# FPGA.net
KiCad netlist of a schematic drawn in Altium Designer
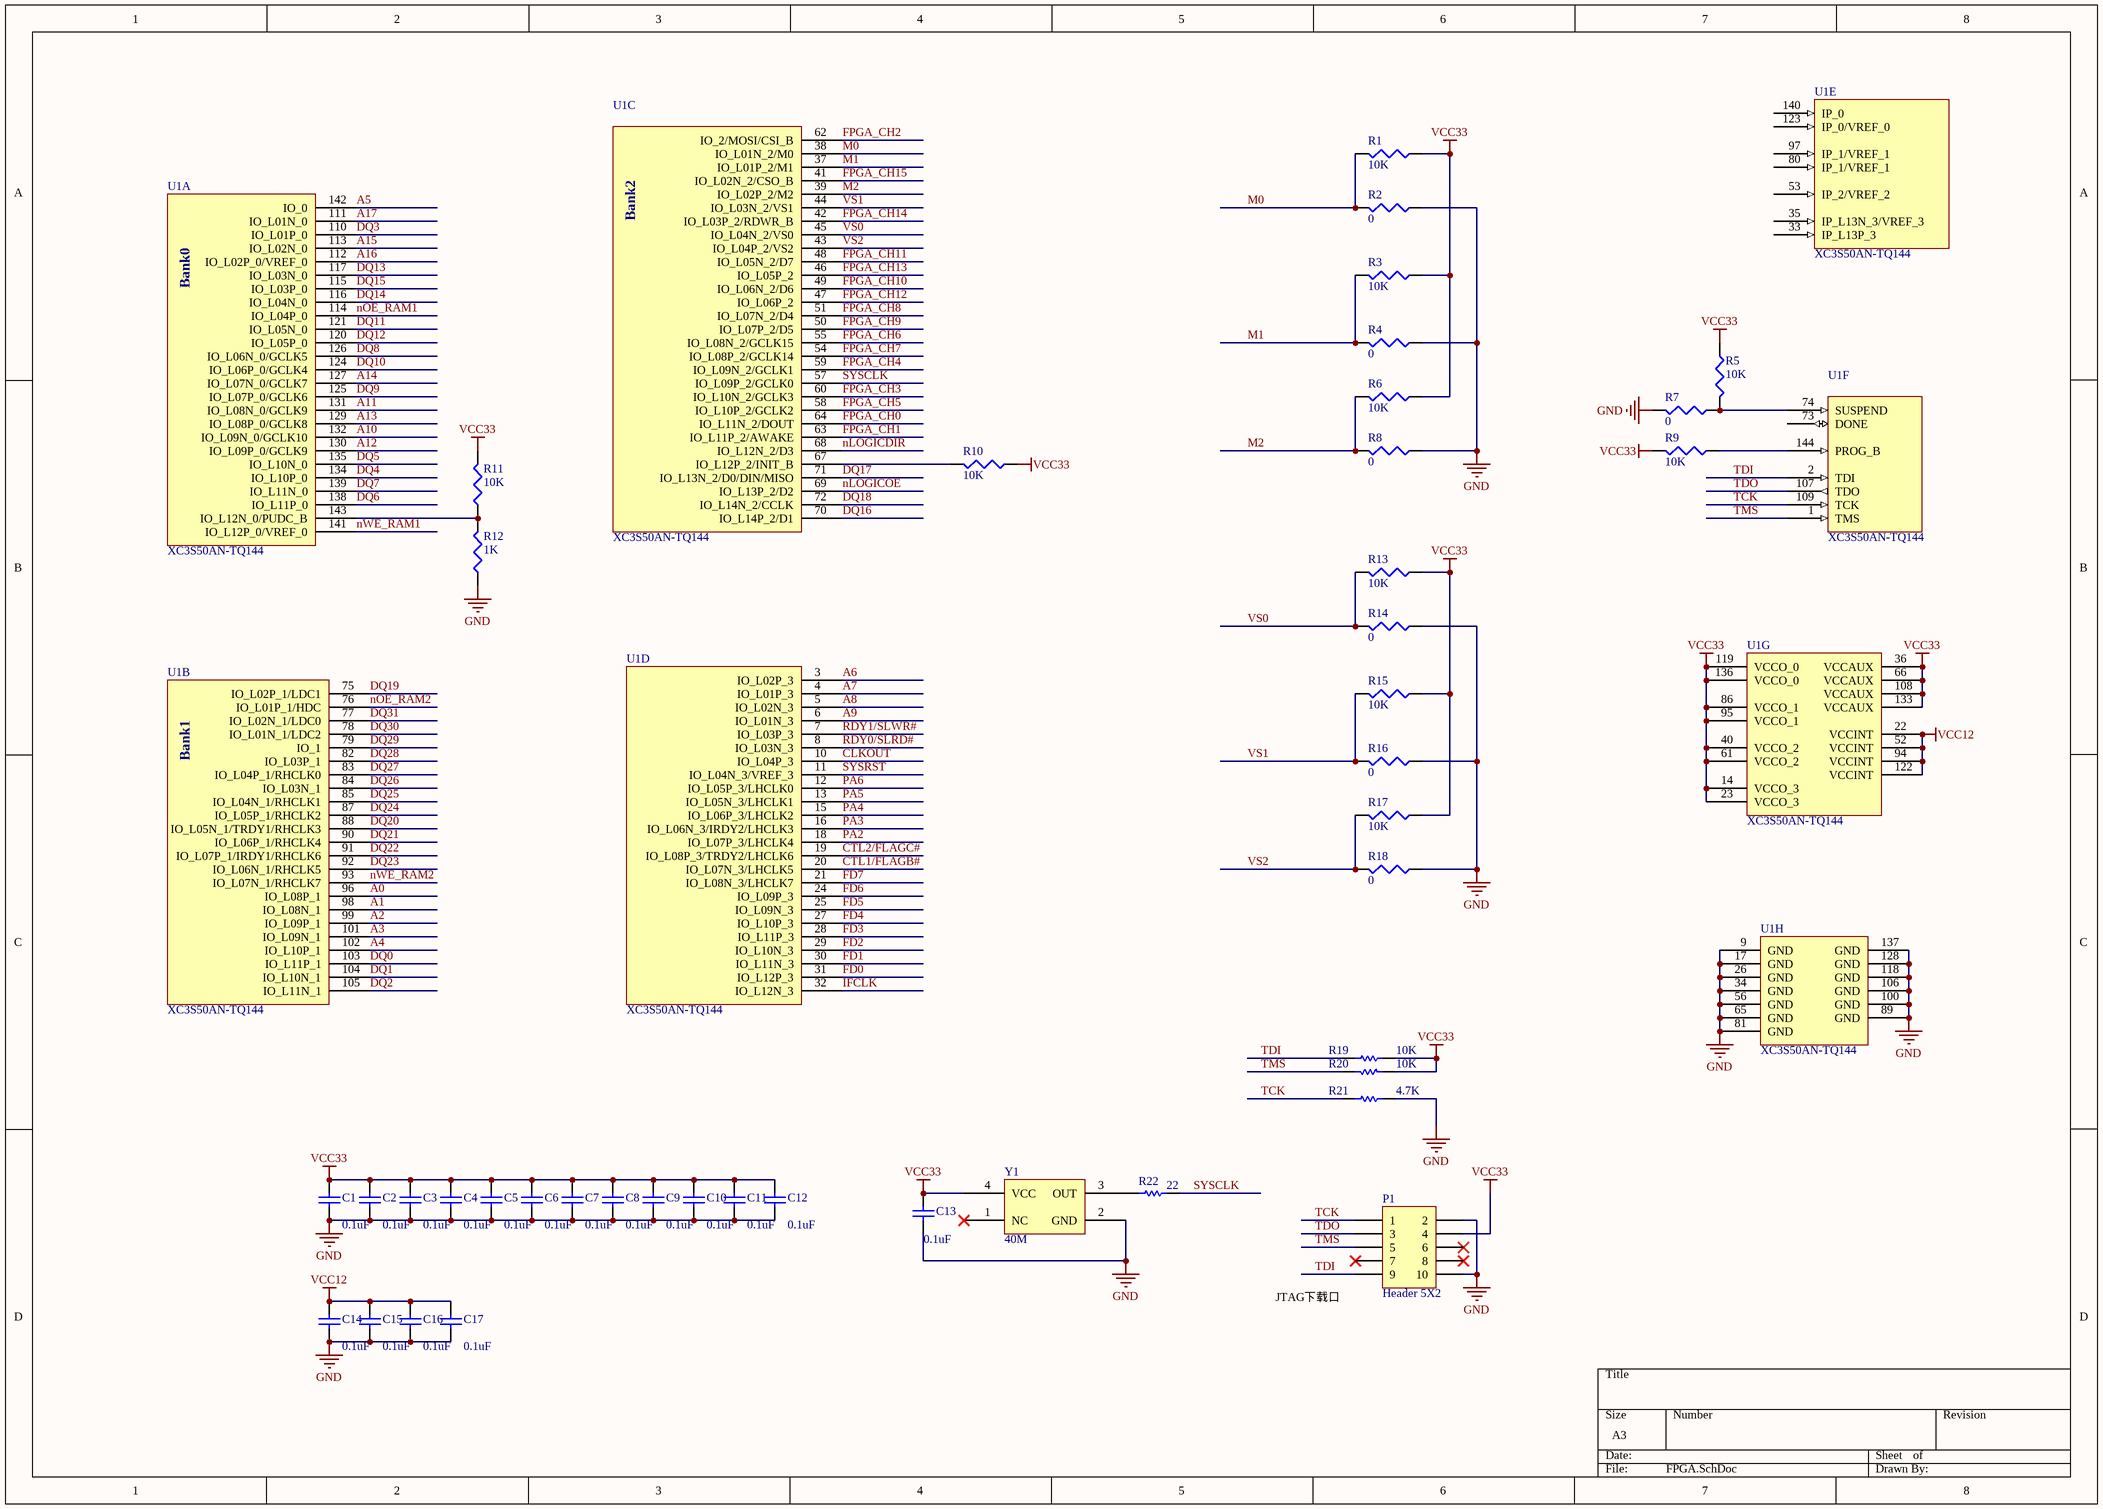
[diagram p0: FPGA.SchDoc]

(export (version "E")
  (design (tool "Eeschema 10.0.6"))
  (components
    (comp (ref "C1")
      (value "0.1uF")
      (footprint "cc0603")
      (description "Capacitor")
      (fields (field (name "PUBLISHER") "Altium Limited"))
      (libsource (lib "Miscellaneous Devices") (part "Cap"))
    )
    (comp (ref "C2")
      (value "0.1uF")
      (footprint "cc0603")
      (description "Capacitor")
      (fields (field (name "PUBLISHER") "Altium Limited"))
      (libsource (lib "Miscellaneous Devices") (part "Cap"))
    )
    (comp (ref "C3")
      (value "0.1uF")
      (footprint "cc0603")
      (description "Capacitor")
      (fields (field (name "PUBLISHER") "Altium Limited"))
      (libsource (lib "Miscellaneous Devices") (part "Cap"))
    )
    (comp (ref "C4")
      (value "0.1uF")
      (footprint "cc0603")
      (description "Capacitor")
      (fields (field (name "PUBLISHER") "Altium Limited"))
      (libsource (lib "Miscellaneous Devices") (part "Cap"))
    )
    (comp (ref "C5")
      (value "0.1uF")
      (footprint "cc0603")
      (description "Capacitor")
      (fields (field (name "PUBLISHER") "Altium Limited"))
      (libsource (lib "Miscellaneous Devices") (part "Cap"))
    )
    (comp (ref "C6")
      (value "0.1uF")
      (footprint "cc0603")
      (description "Capacitor")
      (fields (field (name "PUBLISHER") "Altium Limited"))
      (libsource (lib "Miscellaneous Devices") (part "Cap"))
    )
    (comp (ref "C7")
      (value "0.1uF")
      (footprint "cc0603")
      (description "Capacitor")
      (fields (field (name "PUBLISHER") "Altium Limited"))
      (libsource (lib "Miscellaneous Devices") (part "Cap"))
    )
    (comp (ref "C8")
      (value "0.1uF")
      (footprint "cc0603")
      (description "Capacitor")
      (fields (field (name "PUBLISHER") "Altium Limited"))
      (libsource (lib "Miscellaneous Devices") (part "Cap"))
    )
    (comp (ref "C9")
      (value "0.1uF")
      (footprint "cc0603")
      (description "Capacitor")
      (fields (field (name "PUBLISHER") "Altium Limited"))
      (libsource (lib "Miscellaneous Devices") (part "Cap"))
    )
    (comp (ref "C10")
      (value "0.1uF")
      (footprint "cc0603")
      (description "Capacitor")
      (fields (field (name "PUBLISHER") "Altium Limited"))
      (libsource (lib "Miscellaneous Devices") (part "Cap"))
    )
    (comp (ref "C11")
      (value "0.1uF")
      (footprint "cc0603")
      (description "Capacitor")
      (fields (field (name "PUBLISHER") "Altium Limited"))
      (libsource (lib "Miscellaneous Devices") (part "Cap"))
    )
    (comp (ref "C12")
      (value "0.1uF")
      (footprint "cc0603")
      (description "Capacitor")
      (fields (field (name "PUBLISHER") "Altium Limited"))
      (libsource (lib "Miscellaneous Devices") (part "Cap"))
    )
    (comp (ref "C13")
      (value "0.1uF")
      (footprint "cc0603")
      (description "Capacitor")
      (fields (field (name "PUBLISHER") "Altium Limited"))
      (libsource (lib "Miscellaneous Devices") (part "Cap"))
    )
    (comp (ref "C14")
      (value "0.1uF")
      (footprint "cc0603")
      (description "Capacitor")
      (fields (field (name "PUBLISHER") "Altium Limited"))
      (libsource (lib "Miscellaneous Devices") (part "Cap"))
    )
    (comp (ref "C15")
      (value "0.1uF")
      (footprint "cc0603")
      (description "Capacitor")
      (fields (field (name "PUBLISHER") "Altium Limited"))
      (libsource (lib "Miscellaneous Devices") (part "Cap"))
    )
    (comp (ref "C16")
      (value "0.1uF")
      (footprint "cc0603")
      (description "Capacitor")
      (fields (field (name "PUBLISHER") "Altium Limited"))
      (libsource (lib "Miscellaneous Devices") (part "Cap"))
    )
    (comp (ref "C17")
      (value "0.1uF")
      (footprint "cc0603")
      (description "Capacitor")
      (fields (field (name "PUBLISHER") "Altium Limited"))
      (libsource (lib "Miscellaneous Devices") (part "Cap"))
    )
    (comp (ref "P1")
      (value "Header 5X2")
      (footprint "HDR2X5")
      (description "Header, 5-Pin, Dual row")
      (fields (field (name "PUBLISHER") "Altium Limited"))
      (libsource (lib "Miscellaneous Connectors") (part "Header 5X2"))
    )
    (comp (ref "R1")
      (value "10K")
      (footprint "CR0603")
      (description "Resistor")
      (fields (field (name "PUBLISHER") "Altium Limited"))
      (libsource (lib "Miscellaneous Devices") (part "Res3"))
    )
    (comp (ref "R2")
      (value "0")
      (footprint "CR0603")
      (description "Resistor")
      (fields (field (name "PUBLISHER") "Altium Limited"))
      (libsource (lib "Miscellaneous Devices") (part "Res3"))
    )
    (comp (ref "R3")
      (value "10K")
      (footprint "CR0603")
      (description "Resistor")
      (fields (field (name "PUBLISHER") "Altium Limited"))
      (libsource (lib "Miscellaneous Devices") (part "Res3"))
    )
    (comp (ref "R4")
      (value "0")
      (footprint "CR0603")
      (description "Resistor")
      (fields (field (name "PUBLISHER") "Altium Limited"))
      (libsource (lib "Miscellaneous Devices") (part "Res3"))
    )
    (comp (ref "R5")
      (value "10K")
      (footprint "CR0603")
      (description "Resistor")
      (fields (field (name "PUBLISHER") "Altium Limited"))
      (libsource (lib "Miscellaneous Devices") (part "Res3"))
    )
    (comp (ref "R6")
      (value "10K")
      (footprint "CR0603")
      (description "Resistor")
      (fields (field (name "PUBLISHER") "Altium Limited"))
      (libsource (lib "Miscellaneous Devices") (part "Res3"))
    )
    (comp (ref "R7")
      (value "0")
      (footprint "CR0603")
      (description "Resistor")
      (fields (field (name "PUBLISHER") "Altium Limited"))
      (libsource (lib "Miscellaneous Devices") (part "Res3"))
    )
    (comp (ref "R8")
      (value "0")
      (footprint "CR0603")
      (description "Resistor")
      (fields (field (name "PUBLISHER") "Altium Limited"))
      (libsource (lib "Miscellaneous Devices") (part "Res3"))
    )
    (comp (ref "R9")
      (value "10K")
      (footprint "CR0603")
      (description "Resistor")
      (fields (field (name "PUBLISHER") "Altium Limited"))
      (libsource (lib "Miscellaneous Devices") (part "Res3"))
    )
    (comp (ref "R10")
      (value "10K")
      (footprint "CR0603")
      (description "Resistor")
      (fields (field (name "PUBLISHER") "Altium Limited"))
      (libsource (lib "Miscellaneous Devices") (part "Res3"))
    )
    (comp (ref "R11")
      (value "10K")
      (footprint "CR0603")
      (description "Resistor")
      (fields (field (name "PUBLISHER") "Altium Limited"))
      (libsource (lib "Miscellaneous Devices") (part "Res3"))
    )
    (comp (ref "R12")
      (value "1K")
      (footprint "CR0603")
      (description "Resistor")
      (fields (field (name "PUBLISHER") "Altium Limited"))
      (libsource (lib "Miscellaneous Devices") (part "Res3"))
    )
    (comp (ref "R13")
      (value "10K")
      (footprint "CR0603")
      (description "Resistor")
      (fields (field (name "PUBLISHER") "Altium Limited"))
      (libsource (lib "Miscellaneous Devices") (part "Res3"))
    )
    (comp (ref "R14")
      (value "0")
      (footprint "CR0603")
      (description "Resistor")
      (fields (field (name "PUBLISHER") "Altium Limited"))
      (libsource (lib "Miscellaneous Devices") (part "Res3"))
    )
    (comp (ref "R15")
      (value "10K")
      (footprint "CR0603")
      (description "Resistor")
      (fields (field (name "PUBLISHER") "Altium Limited"))
      (libsource (lib "Miscellaneous Devices") (part "Res3"))
    )
    (comp (ref "R16")
      (value "0")
      (footprint "CR0603")
      (description "Resistor")
      (fields (field (name "PUBLISHER") "Altium Limited"))
      (libsource (lib "Miscellaneous Devices") (part "Res3"))
    )
    (comp (ref "R17")
      (value "10K")
      (footprint "CR0603")
      (description "Resistor")
      (fields (field (name "PUBLISHER") "Altium Limited"))
      (libsource (lib "Miscellaneous Devices") (part "Res3"))
    )
    (comp (ref "R18")
      (value "0")
      (footprint "CR0603")
      (description "Resistor")
      (fields (field (name "PUBLISHER") "Altium Limited"))
      (libsource (lib "Miscellaneous Devices") (part "Res3"))
    )
    (comp (ref "R19")
      (value "10K")
      (footprint "CR0603")
      (description "Resistor")
      (fields (field (name "Comment") "Res1") (field (name "PUBLISHER") "Altium Limited"))
      (libsource (lib "") (part "Res1_1"))
    )
    (comp (ref "R20")
      (value "10K")
      (footprint "CR0603")
      (description "Resistor")
      (fields (field (name "Comment") "Res1") (field (name "PUBLISHER") "Altium Limited"))
      (libsource (lib "") (part "Res1_1"))
    )
    (comp (ref "R21")
      (value "4.7K")
      (footprint "CR0603")
      (description "Resistor")
      (fields (field (name "Comment") "Res1") (field (name "PUBLISHER") "Altium Limited"))
      (libsource (lib "") (part "Res1_1"))
    )
    (comp (ref "R22")
      (value "22")
      (footprint "CR0603")
      (description "Resistor")
      (fields (field (name "Comment") "Res1") (field (name "PUBLISHER") "Altium Limited"))
      (libsource (lib "Miscellaneous Devices") (part "Res1"))
    )
    (comp (ref "U1")
      (value "XC3S50AN-TQ144")
      (footprint "EP2C8T144")
      (libsource (lib "XC3S50AN_TQ144") (part "XC3S50AN-5TQ144"))
    )
    (comp (ref "Y1")
      (value "40M")
      (footprint "jing_zhen(you yuan)")
      (libsource (lib "CLOCK_SOURCE") (part "Component_1"))
    )
  )
  (nets
    (net (code "1") (name "/A0") (class "Default")
      (node (ref "U1") (pin "96") (pinfunction "IO_L08P_1_96") (pintype "passive"))
    )
    (net (code "2") (name "/A1") (class "Default")
      (node (ref "U1") (pin "98") (pinfunction "IO_L08N_1_98") (pintype "passive"))
    )
    (net (code "3") (name "/A2") (class "Default")
      (node (ref "U1") (pin "99") (pinfunction "IO_L09P_1_99") (pintype "passive"))
    )
    (net (code "4") (name "/A3") (class "Default")
      (node (ref "U1") (pin "101") (pinfunction "IO_L09N_1_101") (pintype "passive"))
    )
    (net (code "5") (name "/A4") (class "Default")
      (node (ref "U1") (pin "102") (pinfunction "IO_L10P_1_102") (pintype "passive"))
    )
    (net (code "6") (name "/A5") (class "Default")
      (node (ref "U1") (pin "142") (pinfunction "IO_0_142") (pintype "passive"))
    )
    (net (code "7") (name "/A6") (class "Default")
      (node (ref "U1") (pin "3") (pinfunction "IO_L02P_3_3") (pintype "passive"))
    )
    (net (code "8") (name "/A7") (class "Default")
      (node (ref "U1") (pin "4") (pinfunction "IO_L01P_3_4") (pintype "passive"))
    )
    (net (code "9") (name "/A8") (class "Default")
      (node (ref "U1") (pin "5") (pinfunction "IO_L02N_3_5") (pintype "passive"))
    )
    (net (code "10") (name "/A9") (class "Default")
      (node (ref "U1") (pin "6") (pinfunction "IO_L01N_3_6") (pintype "passive"))
    )
    (net (code "11") (name "/A10") (class "Default")
      (node (ref "U1") (pin "132") (pinfunction "IO_L09N_0/GCLK10_132") (pintype "passive"))
    )
    (net (code "12") (name "/A11") (class "Default")
      (node (ref "U1") (pin "131") (pinfunction "IO_L08N_0/GCLK9_131") (pintype "passive"))
    )
    (net (code "13") (name "/A12") (class "Default")
      (node (ref "U1") (pin "130") (pinfunction "IO_L09P_0/GCLK9_130") (pintype "passive"))
    )
    (net (code "14") (name "/A13") (class "Default")
      (node (ref "U1") (pin "129") (pinfunction "IO_L08P_0/GCLK8_129") (pintype "passive"))
    )
    (net (code "15") (name "/A14") (class "Default")
      (node (ref "U1") (pin "127") (pinfunction "IO_L07N_0/GCLK7_127") (pintype "passive"))
    )
    (net (code "16") (name "/A15") (class "Default")
      (node (ref "U1") (pin "113") (pinfunction "IO_L02N_0_113") (pintype "passive"))
    )
    (net (code "17") (name "/A16") (class "Default")
      (node (ref "U1") (pin "112") (pinfunction "IO_L02P_0/VREF_0_112") (pintype "passive"))
    )
    (net (code "18") (name "/A17") (class "Default")
      (node (ref "U1") (pin "111") (pinfunction "IO_L01N_0_111") (pintype "passive"))
    )
    (net (code "19") (name "/CLKOUT") (class "Default")
      (node (ref "U1") (pin "10") (pinfunction "IO_L04P_3_10") (pintype "passive"))
    )
    (net (code "20") (name "/CTL1{slash}FLAGB#") (class "Default")
      (node (ref "U1") (pin "20") (pinfunction "IO_L07N_3/LHCLK5_20") (pintype "passive"))
    )
    (net (code "21") (name "/CTL2{slash}FLAGC#") (class "Default")
      (node (ref "U1") (pin "19") (pinfunction "IO_L08P_3/TRDY2/LHCLK6_19") (pintype "passive"))
    )
    (net (code "22") (name "/DQ0") (class "Default")
      (node (ref "U1") (pin "103") (pinfunction "IO_L11P_1_103") (pintype "passive"))
    )
    (net (code "23") (name "/DQ1") (class "Default")
      (node (ref "U1") (pin "104") (pinfunction "IO_L10N_1_104") (pintype "passive"))
    )
    (net (code "24") (name "/DQ2") (class "Default")
      (node (ref "U1") (pin "105") (pinfunction "IO_L11N_1_105") (pintype "passive"))
    )
    (net (code "25") (name "/DQ3") (class "Default")
      (node (ref "U1") (pin "110") (pinfunction "IO_L01P_0_110") (pintype "passive"))
    )
    (net (code "26") (name "/DQ4") (class "Default")
      (node (ref "U1") (pin "134") (pinfunction "IO_L10P_0_134") (pintype "passive"))
    )
    (net (code "27") (name "/DQ5") (class "Default")
      (node (ref "U1") (pin "135") (pinfunction "IO_L10N_0_135") (pintype "passive"))
    )
    (net (code "28") (name "/DQ6") (class "Default")
      (node (ref "U1") (pin "138") (pinfunction "IO_L11P_0_138") (pintype "passive"))
    )
    (net (code "29") (name "/DQ7") (class "Default")
      (node (ref "U1") (pin "139") (pinfunction "IO_L11N_0_139") (pintype "passive"))
    )
    (net (code "30") (name "/DQ8") (class "Default")
      (node (ref "U1") (pin "126") (pinfunction "IO_L06N_0/GCLK5_126") (pintype "passive"))
    )
    (net (code "31") (name "/DQ9") (class "Default")
      (node (ref "U1") (pin "125") (pinfunction "IO_L07P_0/GCLK6_125") (pintype "passive"))
    )
    (net (code "32") (name "/DQ10") (class "Default")
      (node (ref "U1") (pin "124") (pinfunction "IO_L06P_0/GCLK4_124") (pintype "passive"))
    )
    (net (code "33") (name "/DQ11") (class "Default")
      (node (ref "U1") (pin "121") (pinfunction "IO_L05N_0_121") (pintype "passive"))
    )
    (net (code "34") (name "/DQ12") (class "Default")
      (node (ref "U1") (pin "120") (pinfunction "IO_L05P_0_120") (pintype "passive"))
    )
    (net (code "35") (name "/DQ13") (class "Default")
      (node (ref "U1") (pin "117") (pinfunction "IO_L03N_0_117") (pintype "passive"))
    )
    (net (code "36") (name "/DQ14") (class "Default")
      (node (ref "U1") (pin "116") (pinfunction "IO_L04N_0_116") (pintype "passive"))
    )
    (net (code "37") (name "/DQ15") (class "Default")
      (node (ref "U1") (pin "115") (pinfunction "IO_L03P_0_115") (pintype "passive"))
    )
    (net (code "38") (name "/DQ16") (class "Default")
      (node (ref "U1") (pin "70") (pinfunction "IO_L14P_2/D1_70") (pintype "passive"))
    )
    (net (code "39") (name "/DQ17") (class "Default")
      (node (ref "U1") (pin "71") (pinfunction "IO_L13N_2/D0/DIN/MISO_71") (pintype "passive"))
    )
    (net (code "40") (name "/DQ18") (class "Default")
      (node (ref "U1") (pin "72") (pinfunction "IO_L14N_2/CCLK_72") (pintype "passive"))
    )
    (net (code "41") (name "/DQ19") (class "Default")
      (node (ref "U1") (pin "75") (pinfunction "IO_L02P_1/LDC1_75") (pintype "passive"))
    )
    (net (code "42") (name "/DQ20") (class "Default")
      (node (ref "U1") (pin "88") (pinfunction "IO_L05N_1/TRDY1/RHCLK3_88") (pintype "passive"))
    )
    (net (code "43") (name "/DQ21") (class "Default")
      (node (ref "U1") (pin "90") (pinfunction "IO_L06P_1/RHCLK4_90") (pintype "passive"))
    )
    (net (code "44") (name "/DQ22") (class "Default")
      (node (ref "U1") (pin "91") (pinfunction "IO_L07P_1/IRDY1/RHCLK6_91") (pintype "passive"))
    )
    (net (code "45") (name "/DQ23") (class "Default")
      (node (ref "U1") (pin "92") (pinfunction "IO_L06N_1/RHCLK5_92") (pintype "passive"))
    )
    (net (code "46") (name "/DQ24") (class "Default")
      (node (ref "U1") (pin "87") (pinfunction "IO_L05P_1/RHCLK2_87") (pintype "passive"))
    )
    (net (code "47") (name "/DQ25") (class "Default")
      (node (ref "U1") (pin "85") (pinfunction "IO_L04N_1/RHCLK1_85") (pintype "passive"))
    )
    (net (code "48") (name "/DQ26") (class "Default")
      (node (ref "U1") (pin "84") (pinfunction "IO_L03N_1_84") (pintype "passive"))
    )
    (net (code "49") (name "/DQ27") (class "Default")
      (node (ref "U1") (pin "83") (pinfunction "IO_L04P_1/RHCLK0_83") (pintype "passive"))
    )
    (net (code "50") (name "/DQ28") (class "Default")
      (node (ref "U1") (pin "82") (pinfunction "IO_L03P_1_82") (pintype "passive"))
    )
    (net (code "51") (name "/DQ29") (class "Default")
      (node (ref "U1") (pin "79") (pinfunction "IO_1_79") (pintype "passive"))
    )
    (net (code "52") (name "/DQ30") (class "Default")
      (node (ref "U1") (pin "78") (pinfunction "IO_L01N_1/LDC2_78") (pintype "passive"))
    )
    (net (code "53") (name "/DQ31") (class "Default")
      (node (ref "U1") (pin "77") (pinfunction "IO_L02N_1/LDC0_77") (pintype "passive"))
    )
    (net (code "54") (name "/FD0") (class "Default")
      (node (ref "U1") (pin "31") (pinfunction "IO_L12P_3_31") (pintype "passive"))
    )
    (net (code "55") (name "/FD1") (class "Default")
      (node (ref "U1") (pin "30") (pinfunction "IO_L11N_3_30") (pintype "passive"))
    )
    (net (code "56") (name "/FD2") (class "Default")
      (node (ref "U1") (pin "29") (pinfunction "IO_L10N_3_29") (pintype "passive"))
    )
    (net (code "57") (name "/FD3") (class "Default")
      (node (ref "U1") (pin "28") (pinfunction "IO_L11P_3_28") (pintype "passive"))
    )
    (net (code "58") (name "/FD4") (class "Default")
      (node (ref "U1") (pin "27") (pinfunction "IO_L10P_3_27") (pintype "passive"))
    )
    (net (code "59") (name "/FD5") (class "Default")
      (node (ref "U1") (pin "25") (pinfunction "IO_L09N_3_25") (pintype "passive"))
    )
    (net (code "60") (name "/FD6") (class "Default")
      (node (ref "U1") (pin "24") (pinfunction "IO_L09P_3_24") (pintype "passive"))
    )
    (net (code "61") (name "/FD7") (class "Default")
      (node (ref "U1") (pin "21") (pinfunction "IO_L08N_3/LHCLK7_21") (pintype "passive"))
    )
    (net (code "62") (name "/FPGA_CH0") (class "Default")
      (node (ref "U1") (pin "64") (pinfunction "IO_L11N_2/DOUT_64") (pintype "passive"))
    )
    (net (code "63") (name "/FPGA_CH1") (class "Default")
      (node (ref "U1") (pin "63") (pinfunction "IO_L11P_2/AWAKE_63") (pintype "passive"))
    )
    (net (code "64") (name "/FPGA_CH2") (class "Default")
      (node (ref "U1") (pin "62") (pinfunction "IO_2/MOSI/CSI_B_62") (pintype "passive"))
    )
    (net (code "65") (name "/FPGA_CH3") (class "Default")
      (node (ref "U1") (pin "60") (pinfunction "IO_L10N_2/GCLK3_60") (pintype "passive"))
    )
    (net (code "66") (name "/FPGA_CH4") (class "Default")
      (node (ref "U1") (pin "59") (pinfunction "IO_L09N_2/GCLK1_59") (pintype "passive"))
    )
    (net (code "67") (name "/FPGA_CH5") (class "Default")
      (node (ref "U1") (pin "58") (pinfunction "IO_L10P_2/GCLK2_58") (pintype "passive"))
    )
    (net (code "68") (name "/FPGA_CH6") (class "Default")
      (node (ref "U1") (pin "55") (pinfunction "IO_L08N_2/GCLK15_55") (pintype "passive"))
    )
    (net (code "69") (name "/FPGA_CH7") (class "Default")
      (node (ref "U1") (pin "54") (pinfunction "IO_L08P_2/GCLK14_54") (pintype "passive"))
    )
    (net (code "70") (name "/FPGA_CH8") (class "Default")
      (node (ref "U1") (pin "51") (pinfunction "IO_L07N_2/D4_51") (pintype "passive"))
    )
    (net (code "71") (name "/FPGA_CH9") (class "Default")
      (node (ref "U1") (pin "50") (pinfunction "IO_L07P_2/D5_50") (pintype "passive"))
    )
    (net (code "72") (name "/FPGA_CH10") (class "Default")
      (node (ref "U1") (pin "49") (pinfunction "IO_L06N_2/D6_49") (pintype "passive"))
    )
    (net (code "73") (name "/FPGA_CH11") (class "Default")
      (node (ref "U1") (pin "48") (pinfunction "IO_L05N_2/D7_48") (pintype "passive"))
    )
    (net (code "74") (name "/FPGA_CH12") (class "Default")
      (node (ref "U1") (pin "47") (pinfunction "IO_L06P_2_47") (pintype "passive"))
    )
    (net (code "75") (name "/FPGA_CH13") (class "Default")
      (node (ref "U1") (pin "46") (pinfunction "IO_L05P_2_46") (pintype "passive"))
    )
    (net (code "76") (name "/FPGA_CH14") (class "Default")
      (node (ref "U1") (pin "42") (pinfunction "IO_L03P_2/RDWR_B_42") (pintype "passive"))
    )
    (net (code "77") (name "/FPGA_CH15") (class "Default")
      (node (ref "U1") (pin "41") (pinfunction "IO_L02N_2/CSO_B_41") (pintype "passive"))
    )
    (net (code "78") (name "/IFCLK") (class "Default")
      (node (ref "U1") (pin "32") (pinfunction "IO_L12N_3_32") (pintype "passive"))
    )
    (net (code "79") (name "/M0") (class "Default")
      (node (ref "R1") (pin "2") (pinfunction "2_2") (pintype "passive"))
      (node (ref "R2") (pin "2") (pinfunction "2_2") (pintype "passive"))
      (node (ref "U1") (pin "38") (pinfunction "IO_L01N_2/M0_38") (pintype "passive"))
    )
    (net (code "80") (name "/M1") (class "Default")
      (node (ref "R3") (pin "2") (pinfunction "2_2") (pintype "passive"))
      (node (ref "R4") (pin "2") (pinfunction "2_2") (pintype "passive"))
      (node (ref "U1") (pin "37") (pinfunction "IO_L01P_2/M1_37") (pintype "passive"))
    )
    (net (code "81") (name "/M2") (class "Default")
      (node (ref "R6") (pin "2") (pinfunction "2_2") (pintype "passive"))
      (node (ref "R8") (pin "2") (pinfunction "2_2") (pintype "passive"))
      (node (ref "U1") (pin "39") (pinfunction "IO_L02P_2/M2_39") (pintype "passive"))
    )
    (net (code "82") (name "/PA2") (class "Default")
      (node (ref "U1") (pin "18") (pinfunction "IO_L07P_3/LHCLK4_18") (pintype "passive"))
    )
    (net (code "83") (name "/PA3") (class "Default")
      (node (ref "U1") (pin "16") (pinfunction "IO_L06N_3/IRDY2/LHCLK3_16") (pintype "passive"))
    )
    (net (code "84") (name "/PA4") (class "Default")
      (node (ref "U1") (pin "15") (pinfunction "IO_L06P_3/LHCLK2_15") (pintype "passive"))
    )
    (net (code "85") (name "/PA5") (class "Default")
      (node (ref "U1") (pin "13") (pinfunction "IO_L05N_3/LHCLK1_13") (pintype "passive"))
    )
    (net (code "86") (name "/PA6") (class "Default")
      (node (ref "U1") (pin "12") (pinfunction "IO_L05P_3/LHCLK0_12") (pintype "passive"))
    )
    (net (code "87") (name "/RDY0{slash}SLRD#") (class "Default")
      (node (ref "U1") (pin "8") (pinfunction "IO_L03N_3_8") (pintype "passive"))
    )
    (net (code "88") (name "/RDY1{slash}SLWR#") (class "Default")
      (node (ref "U1") (pin "7") (pinfunction "IO_L03P_3_7") (pintype "passive"))
    )
    (net (code "89") (name "/SYSCLK") (class "Default")
      (node (ref "R22") (pin "2") (pinfunction "2_2") (pintype "passive"))
      (node (ref "U1") (pin "57") (pinfunction "IO_L09P_2/GCLK0_57") (pintype "passive"))
    )
    (net (code "90") (name "/SYSRST") (class "Default")
      (node (ref "U1") (pin "11") (pinfunction "IO_L04N_3/VREF_3_11") (pintype "passive"))
    )
    (net (code "91") (name "/TCK") (class "Default")
      (node (ref "P1") (pin "1") (pinfunction "1_1") (pintype "passive"))
      (node (ref "R21") (pin "2") (pinfunction "2_2") (pintype "passive"))
      (node (ref "U1") (pin "109") (pinfunction "TCK_109") (pintype "input"))
    )
    (net (code "92") (name "/TDI") (class "Default")
      (node (ref "P1") (pin "9") (pinfunction "9_9") (pintype "passive"))
      (node (ref "R19") (pin "2") (pinfunction "2_2") (pintype "passive"))
      (node (ref "U1") (pin "2") (pinfunction "TDI_2") (pintype "input"))
    )
    (net (code "93") (name "/TDO") (class "Default")
      (node (ref "P1") (pin "3") (pinfunction "3_3") (pintype "passive"))
      (node (ref "U1") (pin "107") (pinfunction "TDO_107") (pintype "output"))
    )
    (net (code "94") (name "/TMS") (class "Default")
      (node (ref "P1") (pin "5") (pinfunction "5_5") (pintype "passive"))
      (node (ref "R20") (pin "2") (pinfunction "2_2") (pintype "passive"))
      (node (ref "U1") (pin "1") (pinfunction "TMS_1") (pintype "input"))
    )
    (net (code "95") (name "/VS0") (class "Default")
      (node (ref "R13") (pin "2") (pinfunction "2_2") (pintype "passive"))
      (node (ref "R14") (pin "2") (pinfunction "2_2") (pintype "passive"))
      (node (ref "U1") (pin "45") (pinfunction "IO_L04N_2/VS0_45") (pintype "passive"))
    )
    (net (code "96") (name "/VS1") (class "Default")
      (node (ref "R15") (pin "2") (pinfunction "2_2") (pintype "passive"))
      (node (ref "R16") (pin "2") (pinfunction "2_2") (pintype "passive"))
      (node (ref "U1") (pin "44") (pinfunction "IO_L03N_2/VS1_44") (pintype "passive"))
    )
    (net (code "97") (name "/VS2") (class "Default")
      (node (ref "R17") (pin "2") (pinfunction "2_2") (pintype "passive"))
      (node (ref "R18") (pin "2") (pinfunction "2_2") (pintype "passive"))
      (node (ref "U1") (pin "43") (pinfunction "IO_L04P_2/VS2_43") (pintype "passive"))
    )
    (net (code "98") (name "/nLOGICDIR") (class "Default")
      (node (ref "U1") (pin "68") (pinfunction "IO_L12N_2/D3_68") (pintype "passive"))
    )
    (net (code "99") (name "/nLOGICOE") (class "Default")
      (node (ref "U1") (pin "69") (pinfunction "IO_L13P_2/D2_69") (pintype "passive"))
    )
    (net (code "100") (name "/nOE_RAM1") (class "Default")
      (node (ref "U1") (pin "114") (pinfunction "IO_L04P_0_114") (pintype "passive"))
    )
    (net (code "101") (name "/nOE_RAM2") (class "Default")
      (node (ref "U1") (pin "76") (pinfunction "IO_L01P_1/HDC_76") (pintype "passive"))
    )
    (net (code "102") (name "/nWE_RAM1") (class "Default")
      (node (ref "U1") (pin "141") (pinfunction "IO_L12P_0/VREF_0_141") (pintype "passive"))
    )
    (net (code "103") (name "/nWE_RAM2") (class "Default")
      (node (ref "U1") (pin "93") (pinfunction "IO_L07N_1/RHCLK7_93") (pintype "passive"))
    )
    (net (code "104") (name "GND") (class "Default")
      (node (ref "C1") (pin "1") (pinfunction "1_1") (pintype "passive"))
      (node (ref "C10") (pin "1") (pinfunction "1_1") (pintype "passive"))
      (node (ref "C11") (pin "1") (pinfunction "1_1") (pintype "passive"))
      (node (ref "C12") (pin "1") (pinfunction "1_1") (pintype "passive"))
      (node (ref "C13") (pin "1") (pinfunction "1_1") (pintype "passive"))
      (node (ref "C14") (pin "1") (pinfunction "1_1") (pintype "passive"))
      (node (ref "C15") (pin "1") (pinfunction "1_1") (pintype "passive"))
      (node (ref "C16") (pin "1") (pinfunction "1_1") (pintype "passive"))
      (node (ref "C17") (pin "1") (pinfunction "1_1") (pintype "passive"))
      (node (ref "C2") (pin "1") (pinfunction "1_1") (pintype "passive"))
      (node (ref "C3") (pin "1") (pinfunction "1_1") (pintype "passive"))
      (node (ref "C4") (pin "1") (pinfunction "1_1") (pintype "passive"))
      (node (ref "C5") (pin "1") (pinfunction "1_1") (pintype "passive"))
      (node (ref "C6") (pin "1") (pinfunction "1_1") (pintype "passive"))
      (node (ref "C7") (pin "1") (pinfunction "1_1") (pintype "passive"))
      (node (ref "C8") (pin "1") (pinfunction "1_1") (pintype "passive"))
      (node (ref "C9") (pin "1") (pinfunction "1_1") (pintype "passive"))
      (node (ref "P1") (pin "10") (pinfunction "10_10") (pintype "passive"))
      (node (ref "P1") (pin "2") (pinfunction "2_2") (pintype "passive"))
      (node (ref "R12") (pin "1") (pinfunction "1_1") (pintype "passive"))
      (node (ref "R14") (pin "1") (pinfunction "1_1") (pintype "passive"))
      (node (ref "R16") (pin "1") (pinfunction "1_1") (pintype "passive"))
      (node (ref "R18") (pin "1") (pinfunction "1_1") (pintype "passive"))
      (node (ref "R2") (pin "1") (pinfunction "1_1") (pintype "passive"))
      (node (ref "R21") (pin "1") (pinfunction "1_1") (pintype "passive"))
      (node (ref "R4") (pin "1") (pinfunction "1_1") (pintype "passive"))
      (node (ref "R7") (pin "2") (pinfunction "2_2") (pintype "passive"))
      (node (ref "R8") (pin "1") (pinfunction "1_1") (pintype "passive"))
      (node (ref "U1") (pin "100") (pinfunction "GND_100") (pintype "passive"))
      (node (ref "U1") (pin "106") (pinfunction "GND_106") (pintype "passive"))
      (node (ref "U1") (pin "118") (pinfunction "GND_118") (pintype "passive"))
      (node (ref "U1") (pin "128") (pinfunction "GND_128") (pintype "passive"))
      (node (ref "U1") (pin "137") (pinfunction "GND_137") (pintype "passive"))
      (node (ref "U1") (pin "17") (pinfunction "GND_17") (pintype "passive"))
      (node (ref "U1") (pin "26") (pinfunction "GND_26") (pintype "passive"))
      (node (ref "U1") (pin "34") (pinfunction "GND_34") (pintype "passive"))
      (node (ref "U1") (pin "56") (pinfunction "GND_56") (pintype "passive"))
      (node (ref "U1") (pin "65") (pinfunction "GND_65") (pintype "passive"))
      (node (ref "U1") (pin "81") (pinfunction "GND_81") (pintype "passive"))
      (node (ref "U1") (pin "89") (pinfunction "GND_89") (pintype "passive"))
      (node (ref "U1") (pin "9") (pinfunction "GND_9") (pintype "passive"))
      (node (ref "Y1") (pin "2") (pinfunction "GND_2") (pintype "power_in"))
    )
    (net (code "105") (name "Net-(U1A-IO_L12N_0{slash}PUDC_B)") (class "Default")
      (node (ref "R11") (pin "1") (pinfunction "1_1") (pintype "passive"))
      (node (ref "R12") (pin "2") (pinfunction "2_2") (pintype "passive"))
      (node (ref "U1") (pin "143") (pinfunction "IO_L12N_0/PUDC_B_143") (pintype "passive"))
    )
    (net (code "106") (name "Net-(U1C-IO_L12P_2{slash}INIT_B)") (class "Default")
      (node (ref "R10") (pin "2") (pinfunction "2_2") (pintype "passive"))
      (node (ref "U1") (pin "67") (pinfunction "IO_L12P_2/INIT_B_67") (pintype "passive"))
    )
    (net (code "107") (name "Net-(U1F-PROG_B)") (class "Default")
      (node (ref "R9") (pin "1") (pinfunction "1_1") (pintype "passive"))
      (node (ref "U1") (pin "144") (pinfunction "PROG_B_144") (pintype "input"))
    )
    (net (code "108") (name "Net-(U1F-SUSPEND)") (class "Default")
      (node (ref "R5") (pin "2") (pinfunction "2_2") (pintype "passive"))
      (node (ref "R7") (pin "1") (pinfunction "1_1") (pintype "passive"))
      (node (ref "U1") (pin "74") (pinfunction "SUSPEND_74") (pintype "input"))
    )
    (net (code "109") (name "Net-(Y1-OUT)") (class "Default")
      (node (ref "R22") (pin "1") (pinfunction "1_1") (pintype "passive"))
      (node (ref "Y1") (pin "3") (pinfunction "OUT_3") (pintype "passive"))
    )
    (net (code "110") (name "VCC12") (class "Default")
      (node (ref "C14") (pin "2") (pinfunction "2_2") (pintype "passive"))
      (node (ref "C15") (pin "2") (pinfunction "2_2") (pintype "passive"))
      (node (ref "C16") (pin "2") (pinfunction "2_2") (pintype "passive"))
      (node (ref "C17") (pin "2") (pinfunction "2_2") (pintype "passive"))
      (node (ref "U1") (pin "122") (pinfunction "VCCINT_122") (pintype "power_in"))
      (node (ref "U1") (pin "22") (pinfunction "VCCINT_22") (pintype "power_in"))
      (node (ref "U1") (pin "52") (pinfunction "VCCINT_52") (pintype "power_in"))
      (node (ref "U1") (pin "94") (pinfunction "VCCINT_94") (pintype "power_in"))
    )
    (net (code "111") (name "VCC33") (class "Default")
      (node (ref "C1") (pin "2") (pinfunction "2_2") (pintype "passive"))
      (node (ref "C10") (pin "2") (pinfunction "2_2") (pintype "passive"))
      (node (ref "C11") (pin "2") (pinfunction "2_2") (pintype "passive"))
      (node (ref "C12") (pin "2") (pinfunction "2_2") (pintype "passive"))
      (node (ref "C13") (pin "2") (pinfunction "2_2") (pintype "passive"))
      (node (ref "C2") (pin "2") (pinfunction "2_2") (pintype "passive"))
      (node (ref "C3") (pin "2") (pinfunction "2_2") (pintype "passive"))
      (node (ref "C4") (pin "2") (pinfunction "2_2") (pintype "passive"))
      (node (ref "C5") (pin "2") (pinfunction "2_2") (pintype "passive"))
      (node (ref "C6") (pin "2") (pinfunction "2_2") (pintype "passive"))
      (node (ref "C7") (pin "2") (pinfunction "2_2") (pintype "passive"))
      (node (ref "C8") (pin "2") (pinfunction "2_2") (pintype "passive"))
      (node (ref "C9") (pin "2") (pinfunction "2_2") (pintype "passive"))
      (node (ref "P1") (pin "4") (pinfunction "4_4") (pintype "passive"))
      (node (ref "R1") (pin "1") (pinfunction "1_1") (pintype "passive"))
      (node (ref "R10") (pin "1") (pinfunction "1_1") (pintype "passive"))
      (node (ref "R11") (pin "2") (pinfunction "2_2") (pintype "passive"))
      (node (ref "R13") (pin "1") (pinfunction "1_1") (pintype "passive"))
      (node (ref "R15") (pin "1") (pinfunction "1_1") (pintype "passive"))
      (node (ref "R17") (pin "1") (pinfunction "1_1") (pintype "passive"))
      (node (ref "R19") (pin "1") (pinfunction "1_1") (pintype "passive"))
      (node (ref "R20") (pin "1") (pinfunction "1_1") (pintype "passive"))
      (node (ref "R3") (pin "1") (pinfunction "1_1") (pintype "passive"))
      (node (ref "R5") (pin "1") (pinfunction "1_1") (pintype "passive"))
      (node (ref "R6") (pin "1") (pinfunction "1_1") (pintype "passive"))
      (node (ref "R9") (pin "2") (pinfunction "2_2") (pintype "passive"))
      (node (ref "U1") (pin "108") (pinfunction "VCCAUX_108") (pintype "power_in"))
      (node (ref "U1") (pin "119") (pinfunction "VCCO_0_119") (pintype "power_in"))
      (node (ref "U1") (pin "133") (pinfunction "VCCAUX_133") (pintype "power_in"))
      (node (ref "U1") (pin "136") (pinfunction "VCCO_0_136") (pintype "power_in"))
      (node (ref "U1") (pin "14") (pinfunction "VCCO_3_14") (pintype "power_in"))
      (node (ref "U1") (pin "23") (pinfunction "VCCO_3_23") (pintype "power_in"))
      (node (ref "U1") (pin "36") (pinfunction "VCCAUX_36") (pintype "power_in"))
      (node (ref "U1") (pin "40") (pinfunction "VCCO_2_40") (pintype "power_in"))
      (node (ref "U1") (pin "61") (pinfunction "VCCO_2_61") (pintype "power_in"))
      (node (ref "U1") (pin "66") (pinfunction "VCCAUX_66") (pintype "power_in"))
      (node (ref "U1") (pin "86") (pinfunction "VCCO_1_86") (pintype "power_in"))
      (node (ref "U1") (pin "95") (pinfunction "VCCO_1_95") (pintype "power_in"))
      (node (ref "Y1") (pin "4") (pinfunction "VCC_4") (pintype "power_in"))
    )
    (net (code "112") (name "unconnected-(P1-Pad6)") (class "Default")
      (node (ref "P1") (pin "6") (pinfunction "6_6") (pintype "passive+no_connect"))
    )
    (net (code "113") (name "unconnected-(P1-Pad7)") (class "Default")
      (node (ref "P1") (pin "7") (pinfunction "7_7") (pintype "passive+no_connect"))
    )
    (net (code "114") (name "unconnected-(P1-Pad8)") (class "Default")
      (node (ref "P1") (pin "8") (pinfunction "8_8") (pintype "passive+no_connect"))
    )
    (net (code "115") (name "unconnected-(U1E-IP_0-Pad140)") (class "Default")
      (node (ref "U1") (pin "140") (pinfunction "IP_0_140") (pintype "input"))
    )
    (net (code "116") (name "unconnected-(U1E-IP_0{slash}VREF_0-Pad123)") (class "Default")
      (node (ref "U1") (pin "123") (pinfunction "IP_0/VREF_0_123") (pintype "input"))
    )
    (net (code "117") (name "unconnected-(U1E-IP_1{slash}VREF_1-Pad80)") (class "Default")
      (node (ref "U1") (pin "80") (pinfunction "IP_1/VREF_1_80") (pintype "input"))
    )
    (net (code "118") (name "unconnected-(U1E-IP_1{slash}VREF_1-Pad97)") (class "Default")
      (node (ref "U1") (pin "97") (pinfunction "IP_1/VREF_1_97") (pintype "input"))
    )
    (net (code "119") (name "unconnected-(U1E-IP_2{slash}VREF_2-Pad53)") (class "Default")
      (node (ref "U1") (pin "53") (pinfunction "IP_2/VREF_2_53") (pintype "input"))
    )
    (net (code "120") (name "unconnected-(U1E-IP_L13N_3{slash}VREF_3-Pad35)") (class "Default")
      (node (ref "U1") (pin "35") (pinfunction "IP_L13N_3/VREF_3_35") (pintype "input"))
    )
    (net (code "121") (name "unconnected-(U1E-IP_L13P_3-Pad33)") (class "Default")
      (node (ref "U1") (pin "33") (pinfunction "IP_L13P_3_33") (pintype "input"))
    )
    (net (code "122") (name "unconnected-(U1F-DONE-Pad73)") (class "Default")
      (node (ref "U1") (pin "73") (pinfunction "DONE_73") (pintype "bidirectional"))
    )
    (net (code "123") (name "unconnected-(Y1-NC-Pad1)") (class "Default")
      (node (ref "Y1") (pin "1") (pinfunction "NC_1") (pintype "passive+no_connect"))
    )
  )
)
